# colpitts.net
KiCad netlist of a schematic drawn in EAGLE
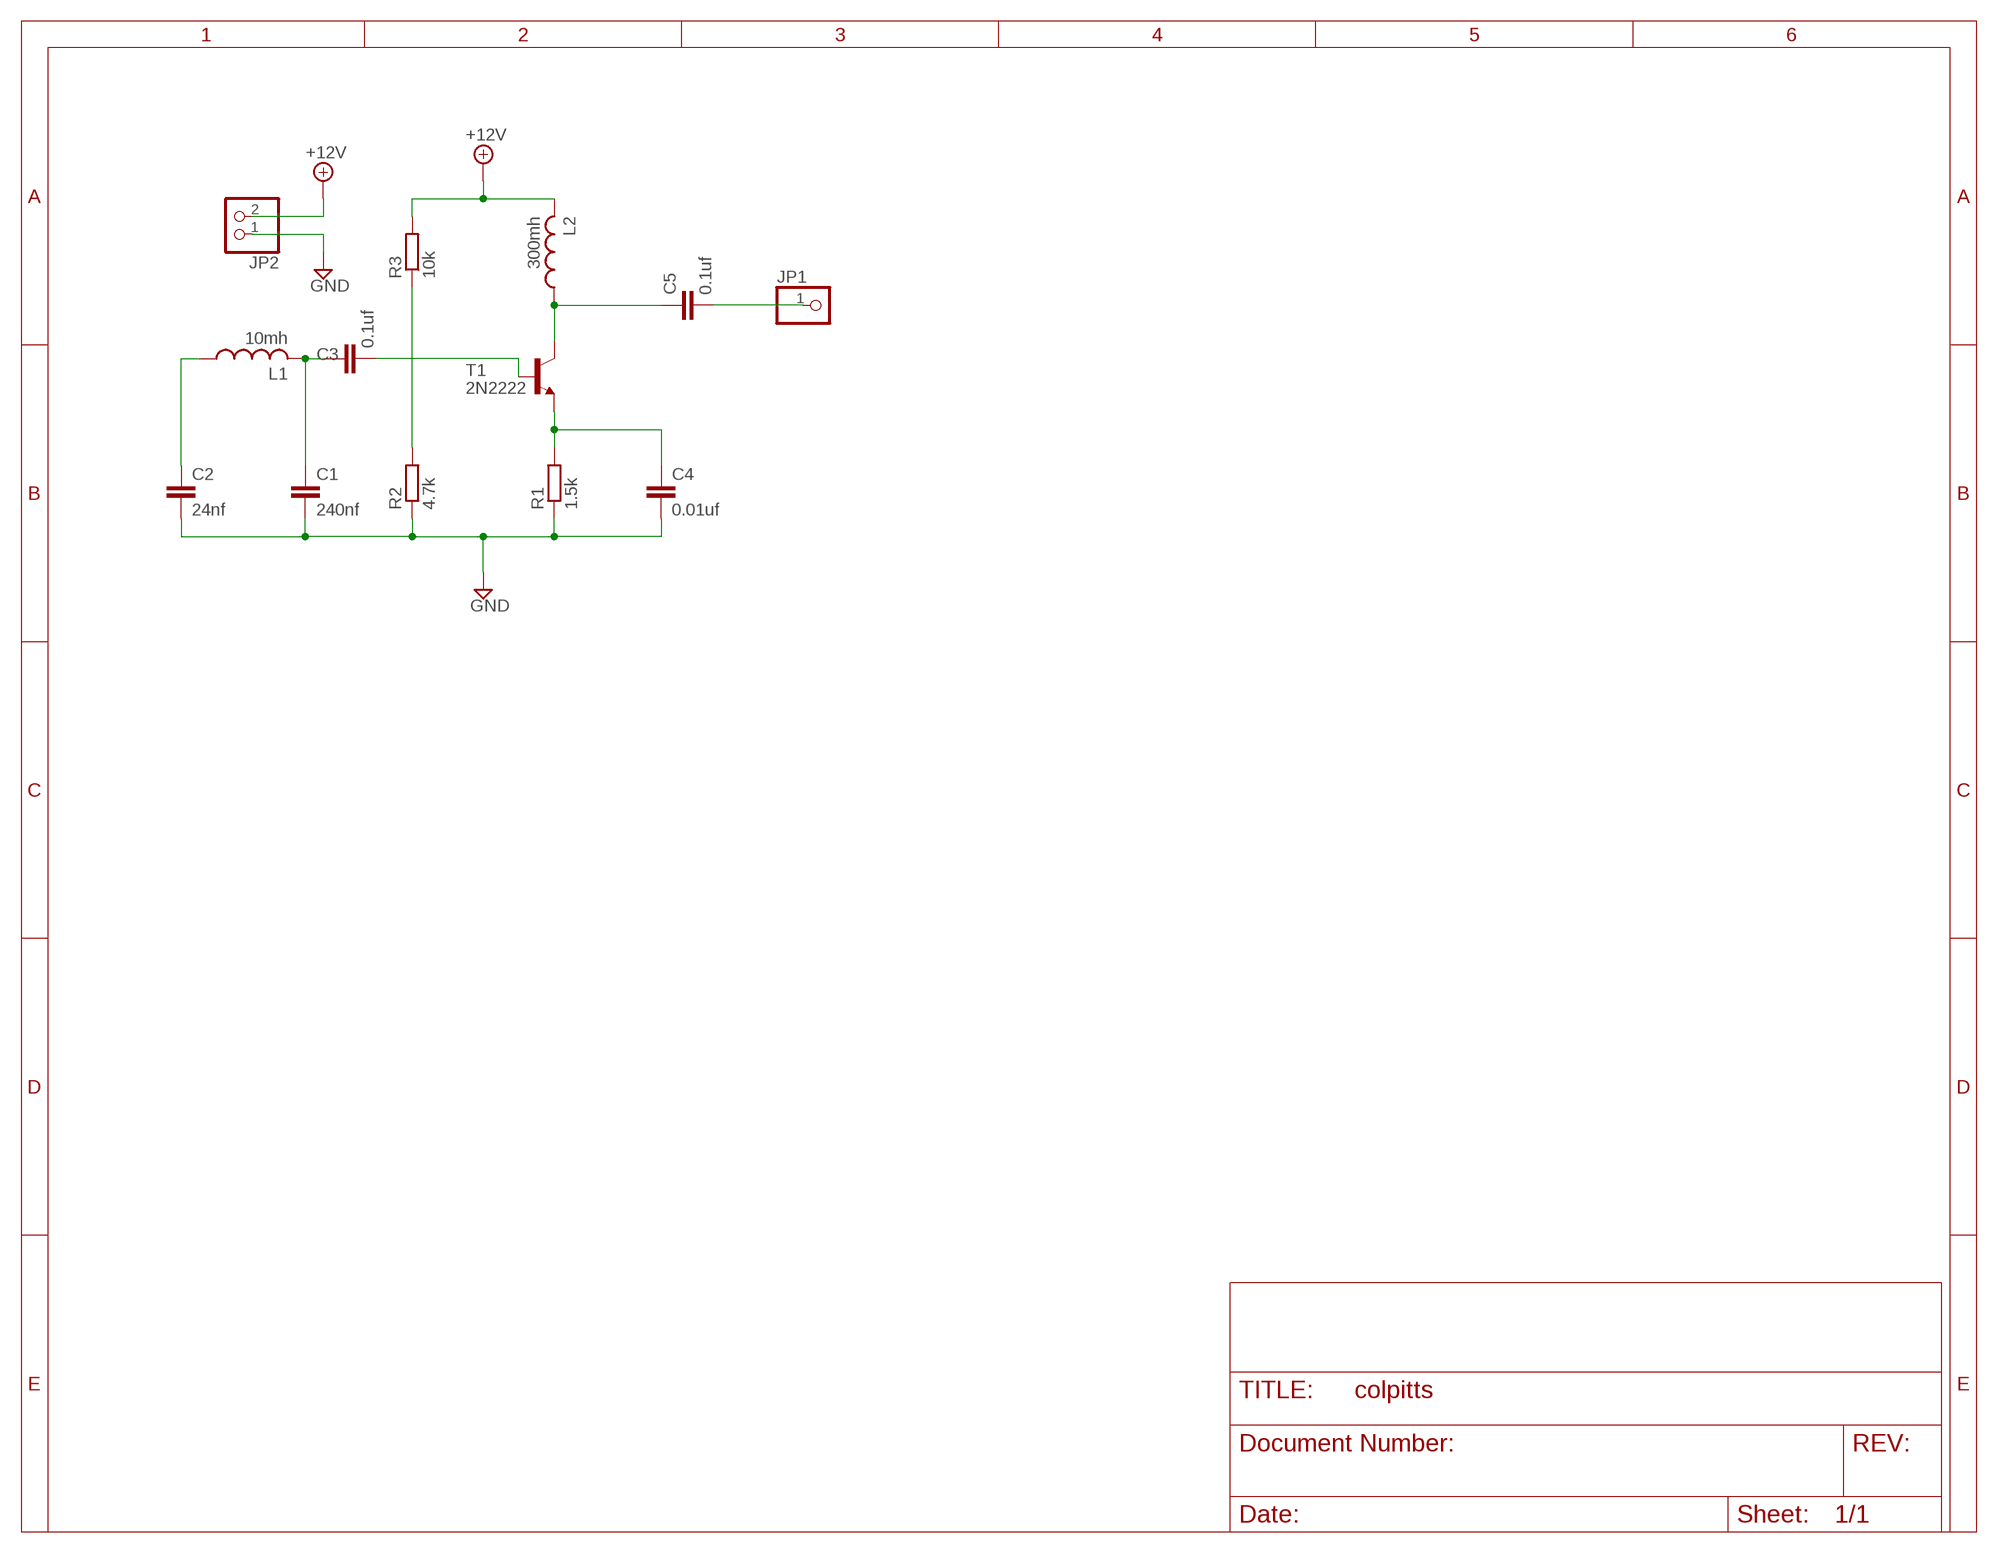
[diagram p0: schematic, sheet 1]

(export (version "E")
  (design (tool "Eeschema 10.0.6"))
  (components
    (comp (ref "C1")
      (value "240nf")
      (footprint "eagle-import:C050-024X044")
      (libsource (lib "eagle-import") (part "C-EU050-024X044"))
    )
    (comp (ref "C2")
      (value "24nf")
      (footprint "eagle-import:C050-024X044")
      (libsource (lib "eagle-import") (part "C-EU050-024X044"))
    )
    (comp (ref "C3")
      (value "0.1uf")
      (footprint "eagle-import:C050-024X044")
      (libsource (lib "eagle-import") (part "C-EU050-024X044"))
    )
    (comp (ref "C4")
      (value "0.01uf")
      (footprint "eagle-import:C050-024X044")
      (libsource (lib "eagle-import") (part "C-EU050-024X044"))
    )
    (comp (ref "C5")
      (value "0.1uf")
      (footprint "eagle-import:C050-024X044")
      (libsource (lib "eagle-import") (part "C-EU050-024X044"))
    )
    (comp (ref "JP1")
      (value "PINHD-1X1")
      (footprint "eagle-import:1X01")
      (libsource (lib "eagle-import") (part "PINHD-1X1"))
    )
    (comp (ref "JP2")
      (value "PINHD-1X2")
      (footprint "eagle-import:1X02")
      (libsource (lib "eagle-import") (part "PINHD-1X2"))
    )
    (comp (ref "L1")
      (value "10mh")
      (footprint "eagle-import:0207_10")
      (libsource (lib "eagle-import") (part "L-US0207/10"))
    )
    (comp (ref "L2")
      (value "300mh")
      (footprint "eagle-import:0207_10")
      (libsource (lib "eagle-import") (part "L-US0207/10"))
    )
    (comp (ref "R1")
      (value "1.5k")
      (footprint "eagle-import:0204_7")
      (libsource (lib "eagle-import") (part "R-EU_0204/7"))
    )
    (comp (ref "R2")
      (value "4.7k")
      (footprint "eagle-import:0204_7")
      (libsource (lib "eagle-import") (part "R-EU_0204/7"))
    )
    (comp (ref "R3")
      (value "10k")
      (footprint "eagle-import:0204_7")
      (libsource (lib "eagle-import") (part "R-EU_0204/7"))
    )
    (comp (ref "T1")
      (value "2N2222")
      (footprint "eagle-import:TO18")
      (libsource (lib "eagle-import") (part "2N2222"))
    )
  )
  (nets
    (net (code "1") (name "+12V") (class "Default")
      (node (ref "JP2") (pin "2") (pinfunction "2_2") (pintype "passive"))
      (node (ref "L2") (pin "2") (pinfunction "2_2") (pintype "passive"))
      (node (ref "R3") (pin "2") (pinfunction "2_2") (pintype "passive"))
    )
    (net (code "2") (name "GND") (class "Default")
      (node (ref "C1") (pin "2") (pinfunction "2_2") (pintype "passive"))
      (node (ref "C2") (pin "2") (pinfunction "2_2") (pintype "passive"))
      (node (ref "C4") (pin "2") (pinfunction "2_2") (pintype "passive"))
      (node (ref "JP2") (pin "1") (pinfunction "1_1") (pintype "passive"))
      (node (ref "R1") (pin "1") (pinfunction "1_1") (pintype "passive"))
      (node (ref "R2") (pin "1") (pinfunction "1_1") (pintype "passive"))
    )
    (net (code "3") (name "Net-(C1-Pad1)") (class "Default")
      (node (ref "C1") (pin "1") (pinfunction "1_1") (pintype "passive"))
      (node (ref "C3") (pin "1") (pinfunction "1_1") (pintype "passive"))
      (node (ref "L1") (pin "2") (pinfunction "2_2") (pintype "passive"))
    )
    (net (code "4") (name "Net-(C2-Pad1)") (class "Default")
      (node (ref "C2") (pin "1") (pinfunction "1_1") (pintype "passive"))
      (node (ref "L1") (pin "1") (pinfunction "1_1") (pintype "passive"))
    )
    (net (code "5") (name "Net-(C5-Pad2)") (class "Default")
      (node (ref "C5") (pin "2") (pinfunction "2_2") (pintype "passive"))
      (node (ref "JP1") (pin "1") (pinfunction "1_1") (pintype "passive"))
    )
    (net (code "6") (name "Net-(R2-Pad2)") (class "Default")
      (node (ref "R2") (pin "2") (pinfunction "2_2") (pintype "passive"))
      (node (ref "R3") (pin "1") (pinfunction "1_1") (pintype "passive"))
    )
    (net (code "7") (name "Net-(T1-B)") (class "Default")
      (node (ref "C3") (pin "2") (pinfunction "2_2") (pintype "passive"))
      (node (ref "T1") (pin "2") (pinfunction "B_2") (pintype "passive"))
    )
    (net (code "8") (name "Net-(T1-C)") (class "Default")
      (node (ref "C5") (pin "1") (pinfunction "1_1") (pintype "passive"))
      (node (ref "L2") (pin "1") (pinfunction "1_1") (pintype "passive"))
      (node (ref "T1") (pin "3") (pinfunction "C_3") (pintype "passive"))
    )
    (net (code "9") (name "Net-(T1-E)") (class "Default")
      (node (ref "C4") (pin "1") (pinfunction "1_1") (pintype "passive"))
      (node (ref "R1") (pin "2") (pinfunction "2_2") (pintype "passive"))
      (node (ref "T1") (pin "1") (pinfunction "E_1") (pintype "passive"))
    )
  )
)
